# Peripherial.net
KiCad netlist of a schematic drawn in Altium Designer
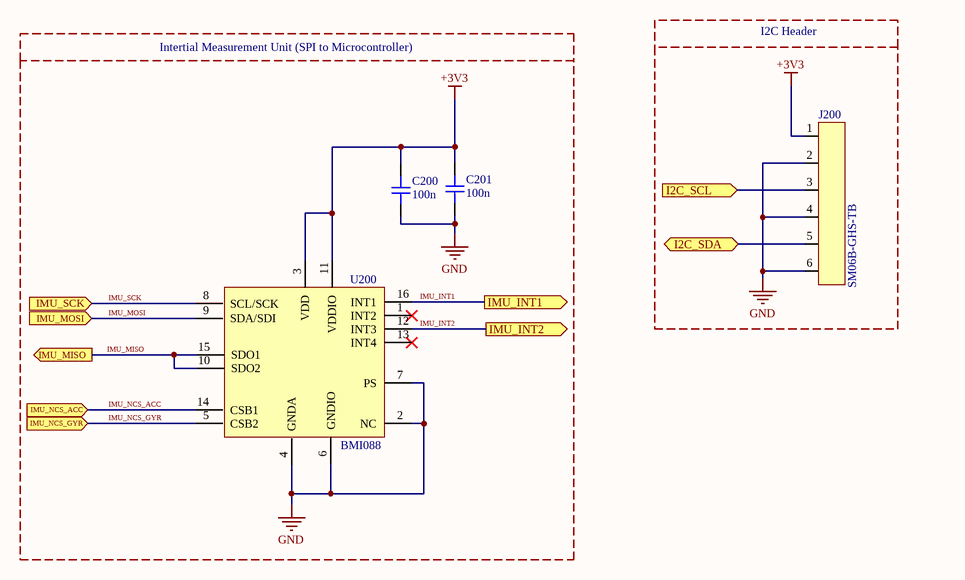
[diagram p0: Peripherial.SchDoc]

(export (version "E")
  (design (tool "Eeschema 10.0.6"))
  (components
    (comp (ref "C200")
      (value "100n")
      (footprint "CAP_0402")
      (description "Capacitor SMD 0402 16V")
      (libsource (lib "Schematic-Lib-Zhrzkn") (part "CAP_0402_16V"))
    )
    (comp (ref "C201")
      (value "100n")
      (footprint "CAP_0402")
      (description "Capacitor SMD 0402 16V")
      (libsource (lib "Schematic-Lib-Zhrzkn") (part "CAP_0402_16V"))
    )
    (comp (ref "J200")
      (value "SM06B-GHS-TB")
      (footprint "SM06B_GHS_TB")
      (description "Header Connector 6 Position 1.25MM Pitch SMD Horizontal JST GH")
      (fields (field (name "MANUFACTURER") "JST"))
      (libsource (lib "Schematic-Lib-Zhrzkn") (part "SM06B-GHS-TB"))
    )
    (comp (ref "U200")
      (value "BMI088")
      (footprint "BMI088")
      (libsource (lib "Schematic-Lib-Zhrzkn") (part "BMI088"))
    )
  )
  (nets
    (net (code "1") (name "+3V3") (class "Default")
      (node (ref "C200") (pin "2") (pinfunction "2_2") (pintype "passive"))
      (node (ref "C201") (pin "2") (pinfunction "2_2") (pintype "passive"))
      (node (ref "J200") (pin "1") (pinfunction "1_1") (pintype "passive"))
      (node (ref "U200") (pin "11") (pinfunction "VDDIO_11") (pintype "passive"))
      (node (ref "U200") (pin "3") (pinfunction "VDD_3") (pintype "passive"))
    )
    (net (code "2") (name "/I2C_SCL") (class "Default")
      (node (ref "J200") (pin "3") (pinfunction "3_3") (pintype "passive"))
    )
    (net (code "3") (name "/I2C_SDA") (class "Default")
      (node (ref "J200") (pin "5") (pinfunction "5_5") (pintype "passive"))
    )
    (net (code "4") (name "/IMU_INT1") (class "Default")
      (node (ref "U200") (pin "16") (pinfunction "INT1_16") (pintype "passive"))
    )
    (net (code "5") (name "/IMU_INT2") (class "Default")
      (node (ref "U200") (pin "12") (pinfunction "INT3_12") (pintype "passive"))
    )
    (net (code "6") (name "/IMU_MISO") (class "Default")
      (node (ref "U200") (pin "10") (pinfunction "SDO2_10") (pintype "passive"))
      (node (ref "U200") (pin "15") (pinfunction "SDO1_15") (pintype "passive"))
    )
    (net (code "7") (name "/IMU_MOSI") (class "Default")
      (node (ref "U200") (pin "9") (pinfunction "SDA/SDI_9") (pintype "passive"))
    )
    (net (code "8") (name "/IMU_NCS_ACC") (class "Default")
      (node (ref "U200") (pin "14") (pinfunction "CSB1_14") (pintype "passive"))
    )
    (net (code "9") (name "/IMU_NCS_GYR") (class "Default")
      (node (ref "U200") (pin "5") (pinfunction "CSB2_5") (pintype "passive"))
    )
    (net (code "10") (name "/IMU_SCK") (class "Default")
      (node (ref "U200") (pin "8") (pinfunction "SCL/SCK_8") (pintype "passive"))
    )
    (net (code "11") (name "GND") (class "Default")
      (node (ref "C200") (pin "1") (pinfunction "1_1") (pintype "passive"))
      (node (ref "C201") (pin "1") (pinfunction "1_1") (pintype "passive"))
      (node (ref "J200") (pin "2") (pinfunction "2_2") (pintype "passive"))
      (node (ref "J200") (pin "4") (pinfunction "4_4") (pintype "passive"))
      (node (ref "J200") (pin "6") (pinfunction "6_6") (pintype "passive"))
      (node (ref "U200") (pin "2") (pinfunction "NC_2") (pintype "passive"))
      (node (ref "U200") (pin "4") (pinfunction "GNDA_4") (pintype "passive"))
      (node (ref "U200") (pin "6") (pinfunction "GNDIO_6") (pintype "passive"))
      (node (ref "U200") (pin "7") (pinfunction "PS_7") (pintype "passive"))
    )
    (net (code "12") (name "unconnected-(U200-INT2-Pad1)") (class "Default")
      (node (ref "U200") (pin "1") (pinfunction "INT2_1") (pintype "passive+no_connect"))
    )
    (net (code "13") (name "unconnected-(U200-INT4-Pad13)") (class "Default")
      (node (ref "U200") (pin "13") (pinfunction "INT4_13") (pintype "passive+no_connect"))
    )
  )
)
